# Salida.net
KiCad netlist of a schematic drawn in Altium Designer
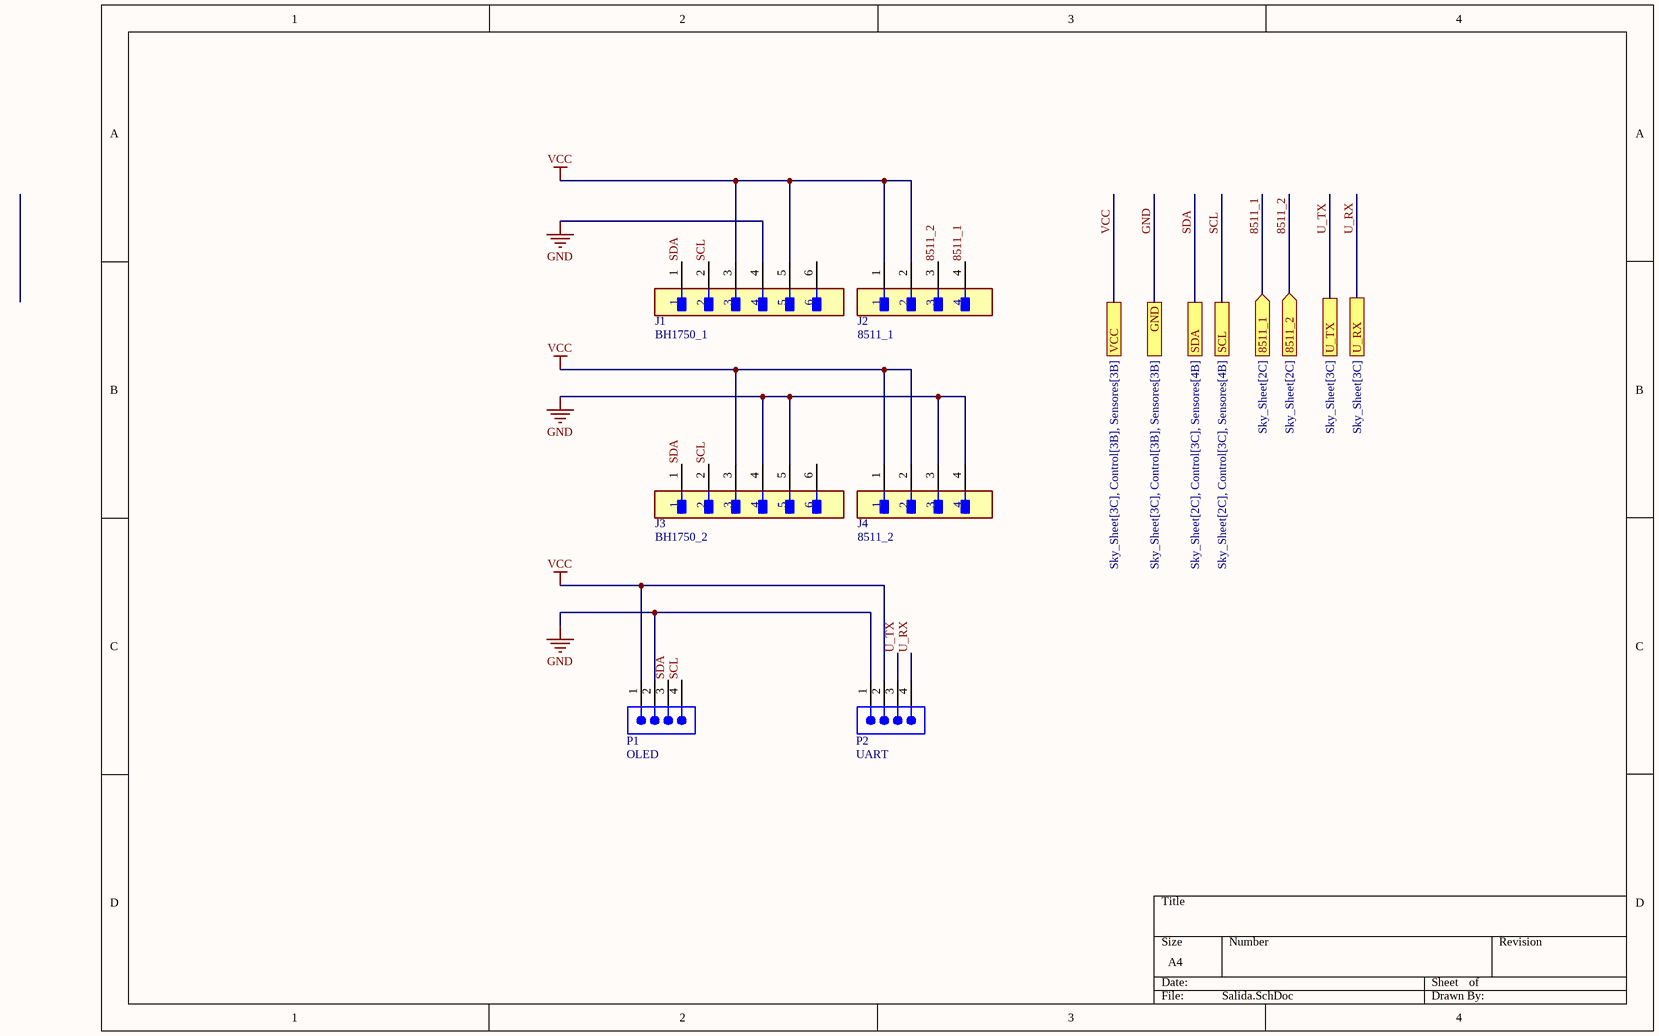
[diagram p0: Salida.SchDoc]

(export (version "E")
  (design (tool "Eeschema 10.0.6"))
  (components
    (comp (ref "J1")
      (value "BH1750_1")
      (footprint "FP-B6B-XH-A_LF_SN-MFG")
      (description "CONN HEADER VERT 6POS 2.5MM")
      (libsource (lib "Altium Content Vault") (part "f2cb566baf1c37ab5a3b8e90bbeafd6"))
    )
    (comp (ref "J2")
      (value "8511_1")
      (footprint "FP-B4B-XH-A_LF_SN-MFG")
      (description "CONN HEADER VERT 4POS 2.5MM")
      (libsource (lib "Altium Content Vault") (part "299a8cea1bdcbc3624fe62c390fa72c"))
    )
    (comp (ref "J3")
      (value "BH1750_2")
      (footprint "FP-B6B-XH-A_LF_SN-MFG")
      (description "CONN HEADER VERT 6POS 2.5MM")
      (libsource (lib "Altium Content Vault") (part "f2cb566baf1c37ab5a3b8e90bbeafd6"))
    )
    (comp (ref "J4")
      (value "8511_2")
      (footprint "FP-B4B-XH-A_LF_SN-MFG")
      (description "CONN HEADER VERT 4POS 2.5MM")
      (libsource (lib "Altium Content Vault") (part "299a8cea1bdcbc3624fe62c390fa72c"))
    )
    (comp (ref "P1")
      (value "OLED")
      (footprint "SMTC-TSW-104-08-X-S")
      (description "0.025\" SQ Post Header, Through-hole, Vertical, -55 to 125 degC, 2.54 mm Pitch, 4-Pin, Male, RoHS")
      (fields (field (name "MANUFACTURER") "Samtec") (field (name "PARTNUMBER") "TSW-104-08-G-S"))
      (libsource (lib "Altium Content Vault") (part "SMTC-TSW-104-08-X-S"))
    )
    (comp (ref "P2")
      (value "UART")
      (footprint "SMTC-TSW-104-08-X-S")
      (description "0.025\" SQ Post Header, Through-hole, Vertical, -55 to 125 degC, 2.54 mm Pitch, 4-Pin, Male, RoHS")
      (fields (field (name "MANUFACTURER") "Samtec") (field (name "PARTNUMBER") "TSW-104-08-G-S"))
      (libsource (lib "Altium Content Vault") (part "SMTC-TSW-104-08-X-S"))
    )
  )
  (nets
    (net (code "1") (name "/8511_1") (class "Default")
      (node (ref "J2") (pin "4") (pinfunction "4_4") (pintype "passive"))
    )
    (net (code "2") (name "/8511_2") (class "Default")
      (node (ref "J2") (pin "3") (pinfunction "3_3") (pintype "passive"))
    )
    (net (code "3") (name "/SCL") (class "Default")
      (node (ref "J1") (pin "2") (pinfunction "2_2") (pintype "passive"))
      (node (ref "J3") (pin "2") (pinfunction "2_2") (pintype "passive"))
      (node (ref "P1") (pin "4") (pinfunction "4_4") (pintype "passive"))
    )
    (net (code "4") (name "/SDA") (class "Default")
      (node (ref "J1") (pin "1") (pinfunction "1_1") (pintype "passive"))
      (node (ref "J3") (pin "1") (pinfunction "1_1") (pintype "passive"))
      (node (ref "P1") (pin "3") (pinfunction "3_3") (pintype "passive"))
    )
    (net (code "5") (name "/U_RX") (class "Default")
      (node (ref "P2") (pin "4") (pinfunction "4_4") (pintype "passive"))
    )
    (net (code "6") (name "/U_TX") (class "Default")
      (node (ref "P2") (pin "3") (pinfunction "3_3") (pintype "passive"))
    )
    (net (code "7") (name "GND") (class "Default")
      (node (ref "J1") (pin "4") (pinfunction "4_4") (pintype "passive"))
      (node (ref "J3") (pin "4") (pinfunction "4_4") (pintype "passive"))
      (node (ref "J3") (pin "5") (pinfunction "5_5") (pintype "passive"))
      (node (ref "J4") (pin "3") (pinfunction "3_3") (pintype "passive"))
      (node (ref "J4") (pin "4") (pinfunction "4_4") (pintype "passive"))
      (node (ref "P1") (pin "2") (pinfunction "2_2") (pintype "passive"))
      (node (ref "P2") (pin "1") (pinfunction "1_1") (pintype "passive"))
    )
    (net (code "8") (name "VCC") (class "Default")
      (node (ref "J1") (pin "3") (pinfunction "3_3") (pintype "passive"))
      (node (ref "J1") (pin "5") (pinfunction "5_5") (pintype "passive"))
      (node (ref "J2") (pin "1") (pinfunction "1_1") (pintype "passive"))
      (node (ref "J2") (pin "2") (pinfunction "2_2") (pintype "passive"))
      (node (ref "J3") (pin "3") (pinfunction "3_3") (pintype "passive"))
      (node (ref "J4") (pin "1") (pinfunction "1_1") (pintype "passive"))
      (node (ref "J4") (pin "2") (pinfunction "2_2") (pintype "passive"))
      (node (ref "P1") (pin "1") (pinfunction "1_1") (pintype "passive"))
      (node (ref "P2") (pin "2") (pinfunction "2_2") (pintype "passive"))
    )
    (net (code "9") (name "unconnected-(J1-Pad6)") (class "Default")
      (node (ref "J1") (pin "6") (pinfunction "6_6") (pintype "passive"))
    )
    (net (code "10") (name "unconnected-(J3-Pad6)") (class "Default")
      (node (ref "J3") (pin "6") (pinfunction "6_6") (pintype "passive"))
    )
  )
)
